# Snippet_TPS73033.net
KiCad netlist of a schematic drawn in Altium Designer
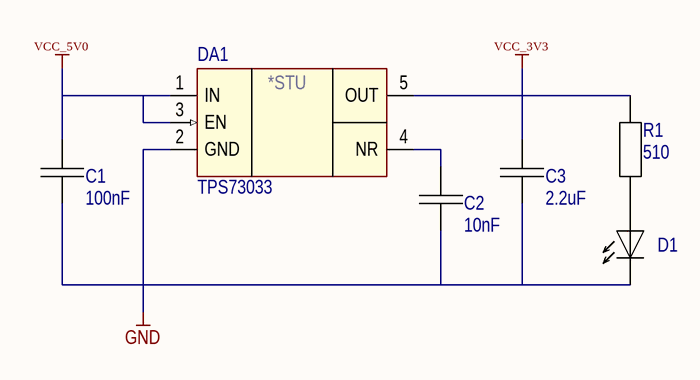
[diagram p0: Snippet_TPS73033.SchDoc]

(export (version "E")
  (design (tool "Eeschema 10.0.6"))
  (components
    (comp (ref "C1")
      (value "100nF")
      (footprint "Capacitor_0805")
      (libsource (lib "Библиотека элементов") (part "Capacitor_0805"))
    )
    (comp (ref "C2")
      (value "10nF")
      (footprint "Capacitor_0805")
      (libsource (lib "Библиотека элементов") (part "Capacitor_0805"))
    )
    (comp (ref "C3")
      (value "2.2uF")
      (footprint "Capacitor_0805")
      (libsource (lib "Библиотека элементов") (part "Capacitor_0805"))
    )
    (comp (ref "D1")
      (value "LED_0805_G")
      (footprint "LED_0805_G")
      (description "KP-2012MGC")
      (libsource (lib "Библиотека элементов") (part "LED_0805_G"))
    )
    (comp (ref "DA1")
      (value "TPS73033")
      (footprint "SOT23-5pin")
      (libsource (lib "Библиотека элементов") (part "TPS73033"))
    )
    (comp (ref "R1")
      (value "510")
      (footprint "RESISTOR_SMD0805")
      (libsource (lib "Библиотека элементов") (part "Resistor_0805"))
    )
  )
  (nets
    (net (code "1") (name "GND") (class "Default")
      (node (ref "C1") (pin "2") (pinfunction "2_2") (pintype "passive"))
      (node (ref "C2") (pin "2") (pinfunction "2_2") (pintype "passive"))
      (node (ref "C3") (pin "2") (pinfunction "2_2") (pintype "passive"))
      (node (ref "D1") (pin "2") (pinfunction "2_2") (pintype "passive"))
      (node (ref "DA1") (pin "2") (pinfunction "GND_2") (pintype "power_in"))
    )
    (net (code "2") (name "Net-(D1-Pad1)") (class "Default")
      (node (ref "D1") (pin "1") (pinfunction "1_1") (pintype "passive"))
      (node (ref "R1") (pin "2") (pinfunction "2_2") (pintype "passive"))
    )
    (net (code "3") (name "Net-(DA1-NR)") (class "Default")
      (node (ref "C2") (pin "1") (pinfunction "1_1") (pintype "passive"))
      (node (ref "DA1") (pin "4") (pinfunction "NR_4") (pintype "power_in"))
    )
    (net (code "4") (name "VCC_3V3") (class "Default")
      (node (ref "C3") (pin "1") (pinfunction "1_1") (pintype "passive"))
      (node (ref "DA1") (pin "5") (pinfunction "OUT_5") (pintype "power_in"))
      (node (ref "R1") (pin "1") (pinfunction "1_1") (pintype "passive"))
    )
    (net (code "5") (name "VCC_5V0") (class "Default")
      (node (ref "C1") (pin "1") (pinfunction "1_1") (pintype "passive"))
      (node (ref "DA1") (pin "1") (pinfunction "IN_1") (pintype "power_in"))
      (node (ref "DA1") (pin "3") (pinfunction "EN_3") (pintype "input"))
    )
  )
)
